# SAM9X60_Core.net
KiCad netlist of a schematic drawn in Altium Designer
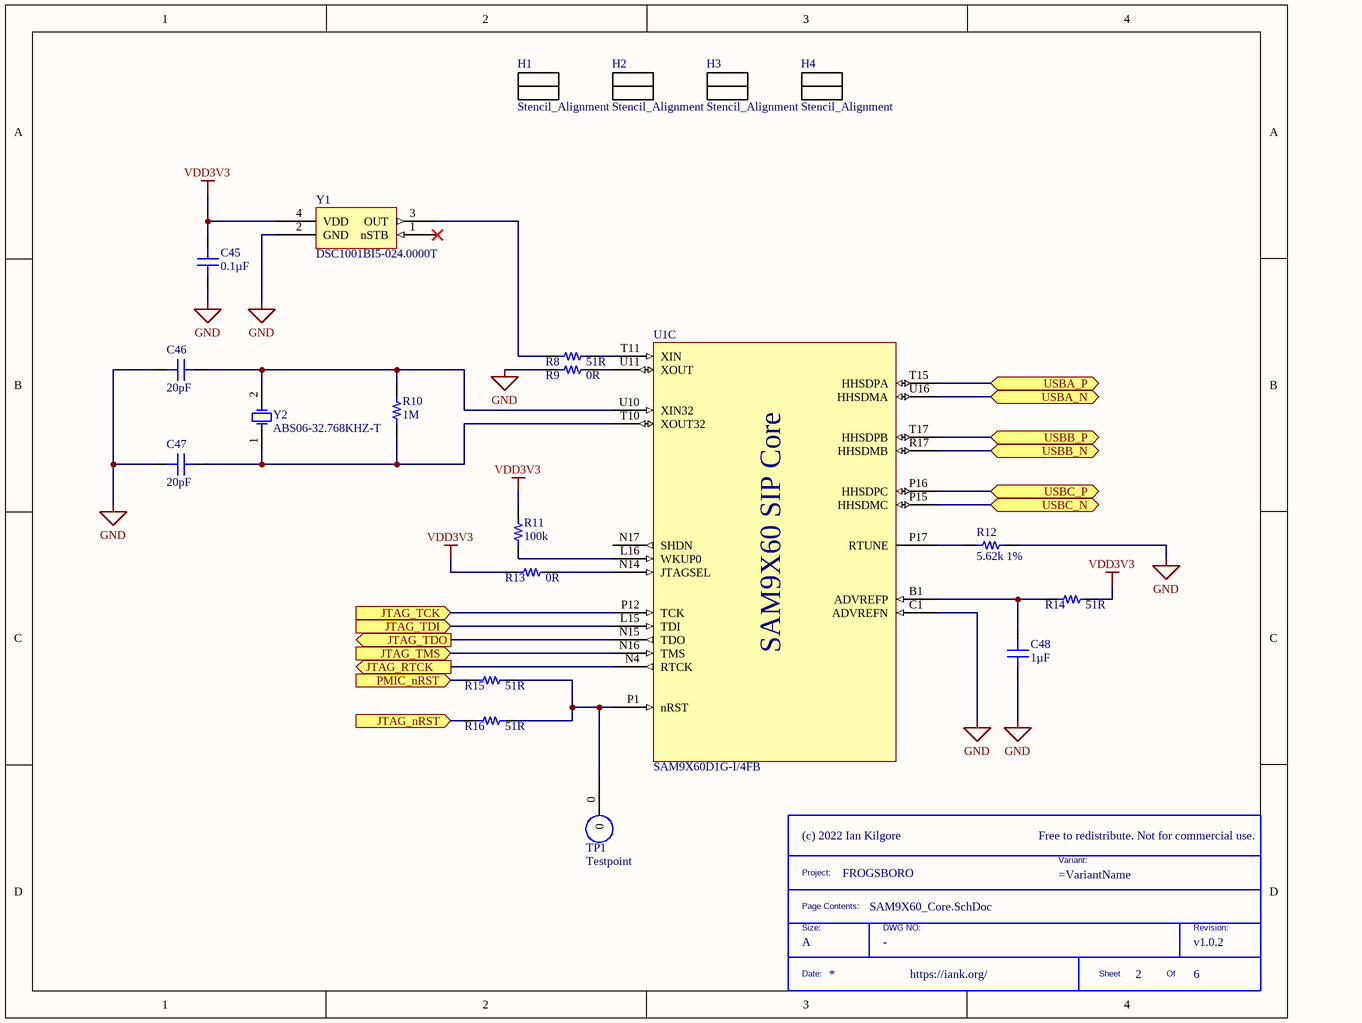
[diagram p0: SAM9X60_Core.SchDoc]

(export (version "E")
  (design (tool "Eeschema 10.0.6"))
  (components
    (comp (ref "C45")
      (value "0.1µF")
      (footprint "CAP 0402_1005")
      (description "CAP CER 0.1UF 16V X5R 0402")
      (fields (field (name "PART NUMBER") "C0402C104K4PACTU") (field (name "MANUFACTURER") "KEMET"))
      (libsource (lib "Celestial Altium Library - altium_library") (part "Capacitor"))
    )
    (comp (ref "C46")
      (value "20pF")
      (footprint "CAP 0402_1005")
      (description "CAP CER 20PF 50V C0G/NP0 0402")
      (fields
        (field (name "PART NUMBER") "GJM1555C1H200FB01D")
        (field (name "MANUFACTURER") "Murata Electronics")
      )
      (libsource (lib "Celestial Altium Library - altium_library") (part "Capacitor"))
    )
    (comp (ref "C47")
      (value "20pF")
      (footprint "CAP 0402_1005")
      (description "CAP CER 20PF 50V C0G/NP0 0402")
      (fields
        (field (name "PART NUMBER") "GJM1555C1H200FB01D")
        (field (name "MANUFACTURER") "Murata Electronics")
      )
      (libsource (lib "Celestial Altium Library - altium_library") (part "Capacitor"))
    )
    (comp (ref "C48")
      (value "1µF")
      (footprint "CAP 0402_1005")
      (description "CAP CER 1UF 10V X5R 0402")
      (fields (field (name "PART NUMBER") "0402ZD105KAT2A") (field (name "MANUFACTURER") "AVX Corporation"))
      (libsource (lib "Celestial Altium Library - altium_library") (part "Capacitor"))
    )
    (comp (ref "H1")
      (value "Stencil_Alignment")
      (footprint "Stencil_Alignment")
      (libsource (lib "FROGSBORO") (part "Stencil_Alignment"))
    )
    (comp (ref "H2")
      (value "Stencil_Alignment")
      (footprint "Stencil_Alignment")
      (libsource (lib "FROGSBORO") (part "Stencil_Alignment"))
    )
    (comp (ref "H3")
      (value "Stencil_Alignment")
      (footprint "Stencil_Alignment")
      (libsource (lib "FROGSBORO") (part "Stencil_Alignment"))
    )
    (comp (ref "H4")
      (value "Stencil_Alignment")
      (footprint "Stencil_Alignment")
      (libsource (lib "FROGSBORO") (part "Stencil_Alignment"))
    )
    (comp (ref "R8")
      (value "51R")
      (footprint "RES 0402_1005")
      (description "RES SMD 51 OHM 1% 1/16W 0402")
      (fields (field (name "PART NUMBER") "AC0402FR-0751RL") (field (name "MANUFACTURER") "Yageo"))
      (libsource (lib "Celestial Altium Library - altium_library") (part "Resistor"))
    )
    (comp (ref "R9")
      (value "0R")
      (footprint "RES 0402_1005")
      (description "RES SMD 0 OHM JUMPER 1/16W 0402")
      (fields
        (field (name "PART NUMBER") "CRG0402ZR")
        (field (name "MANUFACTURER") "TE Connectivity Passive Product")
      )
      (libsource (lib "Celestial Altium Library - altium_library") (part "Resistor"))
    )
    (comp (ref "R10")
      (value "1M")
      (footprint "RES 0402_1005")
      (description "RES SMD 1M OHM 5% 1/5W 0402")
      (fields (field (name "PART NUMBER") "RCS04021M00JNED") (field (name "MANUFACTURER") "Vishay Dale"))
      (libsource (lib "Celestial Altium Library - altium_library") (part "Resistor"))
    )
    (comp (ref "R11")
      (value "100k")
      (footprint "RES 0402_1005")
      (description "RES SMD 100K OHM 1% 1/16W 0402")
      (fields (field (name "PART NUMBER") "CRCW0402100KFKEDC") (field (name "MANUFACTURER") "Vishay Dale"))
      (libsource (lib "Celestial Altium Library - altium_library") (part "Resistor"))
    )
    (comp (ref "R12")
      (value "5.62k 1%")
      (footprint "RES 0402_1005")
      (description "RES SMD 5.62K OHM 1% 1/16W 0402")
      (fields (field (name "PART NUMBER") "AC0402FR-075K62L") (field (name "MANUFACTURER") "Yageo"))
      (libsource (lib "Celestial Altium Library - altium_library") (part "Resistor"))
    )
    (comp (ref "R13")
      (value "0R")
      (footprint "RES 0402_1005")
      (description "RES SMD 0 OHM JUMPER 1/16W 0402")
      (fields
        (field (name "PART NUMBER") "CRG0402ZR")
        (field (name "MANUFACTURER") "TE Connectivity Passive Product")
      )
      (libsource (lib "Celestial Altium Library - altium_library") (part "Resistor"))
    )
    (comp (ref "R14")
      (value "51R")
      (footprint "RES 0402_1005")
      (description "RES SMD 51 OHM 1% 1/16W 0402")
      (fields (field (name "PART NUMBER") "AC0402FR-0751RL") (field (name "MANUFACTURER") "Yageo"))
      (libsource (lib "Celestial Altium Library - altium_library") (part "Resistor"))
    )
    (comp (ref "R15")
      (value "51R")
      (footprint "RES 0402_1005")
      (description "RES SMD 51 OHM 1% 1/16W 0402")
      (fields (field (name "PART NUMBER") "AC0402FR-0751RL") (field (name "MANUFACTURER") "Yageo"))
      (libsource (lib "Celestial Altium Library - altium_library") (part "Resistor"))
    )
    (comp (ref "R16")
      (value "51R")
      (footprint "RES 0402_1005")
      (description "RES SMD 51 OHM 1% 1/16W 0402")
      (fields (field (name "PART NUMBER") "AC0402FR-0751RL") (field (name "MANUFACTURER") "Yageo"))
      (libsource (lib "Celestial Altium Library - altium_library") (part "Resistor"))
    )
    (comp (ref "TP1")
      (value "Testpoint")
      (footprint "FROGSBORO:Testpoint")
      (libsource (lib "FROGSBORO") (part "Testpoint"))
    )
    (comp (ref "U1")
      (value "SAM9X60D1G-I/4FB")
      (footprint "FROGSBORO:BGA233C80P17X17_1400X1400X120")
      (description "ARM926 MPU, 1GBIT DDR2, BGA, IND TEMP")
      (fields
        (field (name "MANUFACTURER") "Microchip")
        (field (name "MANUFACTURER PART NUMBER") "SAM9X60D6K-I/4GB")
      )
      (libsource (lib "FROGSBORO") (part "SAM9X60D1G-I/4FB"))
    )
    (comp (ref "Y1")
      (value "DSC1001BI5-024.0000T")
      (footprint "FROGSBORO:DSC1001BI5")
      (description "Low-Power Precision CMOS Oscillator 24MHz 1.7V to 3.6V 10ppm 4-Pin Surface Mount T/R")
      (fields (field (name "MANUFACTURER") "Microchip"))
      (libsource (lib "FROGSBORO") (part "DSC1001BI5-024.0000T"))
    )
    (comp (ref "Y2")
      (value "ABS06-32.768KHZ-T")
      (footprint "ABRA-ABS06-2_V")
      (description "Low Profile Crystal, 32.768 KHz, -40 to 85 degC, 2-Pin SMD, RoHS, Tape and Reel")
      (fields (field (name "TOLERANCE") "20PPM") (field (name "MANUFACTURER") "ABRACON"))
      (libsource (lib "Altium Content Vault") (part "XTAL_1-2-2"))
    )
  )
  (nets
    (net (code "1") (name "/JTAG_RTCK") (class "Default")
      (node (ref "U1") (pin "N4") (pinfunction "RTCK_N4") (pintype "output"))
    )
    (net (code "2") (name "/JTAG_TCK") (class "Default")
      (node (ref "U1") (pin "P12") (pinfunction "TCK_P12") (pintype "input"))
    )
    (net (code "3") (name "/JTAG_TDI") (class "Default")
      (node (ref "U1") (pin "L15") (pinfunction "TDI_L15") (pintype "input"))
    )
    (net (code "4") (name "/JTAG_TDO") (class "Default")
      (node (ref "U1") (pin "N15") (pinfunction "TDO_N15") (pintype "output"))
    )
    (net (code "5") (name "/JTAG_TMS") (class "Default")
      (node (ref "U1") (pin "N16") (pinfunction "TMS_N16") (pintype "input"))
    )
    (net (code "6") (name "/JTAG_nRST") (class "Default")
      (node (ref "R16") (pin "1") (pinfunction "1_1") (pintype "passive"))
    )
    (net (code "7") (name "/PMIC_nRST") (class "Default")
      (node (ref "R15") (pin "1") (pinfunction "1_1") (pintype "passive"))
    )
    (net (code "8") (name "/USBA_N") (class "Default")
      (node (ref "U1") (pin "U16") (pinfunction "HHSDMA_U16") (pintype "bidirectional"))
    )
    (net (code "9") (name "/USBA_P") (class "Default")
      (node (ref "U1") (pin "T15") (pinfunction "HHSDPA_T15") (pintype "bidirectional"))
    )
    (net (code "10") (name "/USBB_N") (class "Default")
      (node (ref "U1") (pin "R17") (pinfunction "HHSDMB_R17") (pintype "bidirectional"))
    )
    (net (code "11") (name "/USBB_P") (class "Default")
      (node (ref "U1") (pin "T17") (pinfunction "HHSDPB_T17") (pintype "bidirectional"))
    )
    (net (code "12") (name "/USBC_N") (class "Default")
      (node (ref "U1") (pin "P15") (pinfunction "HHSDMC_P15") (pintype "bidirectional"))
    )
    (net (code "13") (name "/USBC_P") (class "Default")
      (node (ref "U1") (pin "P16") (pinfunction "HHSDPC_P16") (pintype "bidirectional"))
    )
    (net (code "14") (name "GND") (class "Default")
      (node (ref "C45") (pin "2") (pinfunction "2_2") (pintype "passive"))
      (node (ref "C46") (pin "1") (pinfunction "1_1") (pintype "passive"))
      (node (ref "C47") (pin "1") (pinfunction "1_1") (pintype "passive"))
      (node (ref "C48") (pin "1") (pinfunction "1_1") (pintype "passive"))
      (node (ref "R12") (pin "2") (pinfunction "2_2") (pintype "passive"))
      (node (ref "R9") (pin "1") (pinfunction "1_1") (pintype "passive"))
      (node (ref "U1") (pin "C1") (pinfunction "ADVREFN_C1") (pintype "input"))
      (node (ref "Y1") (pin "2") (pinfunction "GND_2") (pintype "power_in"))
    )
    (net (code "15") (name "Net-(U1C-ADVREFP)") (class "Default")
      (node (ref "C48") (pin "2") (pinfunction "2_2") (pintype "passive"))
      (node (ref "R14") (pin "1") (pinfunction "1_1") (pintype "passive"))
      (node (ref "U1") (pin "B1") (pinfunction "ADVREFP_B1") (pintype "input"))
    )
    (net (code "16") (name "Net-(U1C-JTAGSEL)") (class "Default")
      (node (ref "R13") (pin "2") (pinfunction "2_2") (pintype "passive"))
      (node (ref "U1") (pin "N14") (pinfunction "JTAGSEL_N14") (pintype "input"))
    )
    (net (code "17") (name "Net-(U1C-RTUNE)") (class "Default")
      (node (ref "R12") (pin "1") (pinfunction "1_1") (pintype "passive"))
      (node (ref "U1") (pin "P17") (pinfunction "RTUNE_P17") (pintype "passive"))
    )
    (net (code "18") (name "Net-(U1C-WKUP0)") (class "Default")
      (node (ref "R11") (pin "1") (pinfunction "1_1") (pintype "passive"))
      (node (ref "U1") (pin "L16") (pinfunction "WKUP0_L16") (pintype "input"))
    )
    (net (code "19") (name "Net-(U1C-XIN)") (class "Default")
      (node (ref "R8") (pin "2") (pinfunction "2_2") (pintype "passive"))
      (node (ref "U1") (pin "T11") (pinfunction "XIN_T11") (pintype "input"))
    )
    (net (code "20") (name "Net-(U1C-XIN32)") (class "Default")
      (node (ref "C46") (pin "2") (pinfunction "2_2") (pintype "passive"))
      (node (ref "R10") (pin "2") (pinfunction "2_2") (pintype "passive"))
      (node (ref "U1") (pin "U10") (pinfunction "XIN32_U10") (pintype "input"))
      (node (ref "Y2") (pin "2") (pinfunction "X2_2") (pintype "passive"))
    )
    (net (code "21") (name "Net-(U1C-XOUT)") (class "Default")
      (node (ref "R9") (pin "2") (pinfunction "2_2") (pintype "passive"))
      (node (ref "U1") (pin "U11") (pinfunction "XOUT_U11") (pintype "bidirectional"))
    )
    (net (code "22") (name "Net-(U1C-XOUT32)") (class "Default")
      (node (ref "C47") (pin "2") (pinfunction "2_2") (pintype "passive"))
      (node (ref "R10") (pin "1") (pinfunction "1_1") (pintype "passive"))
      (node (ref "U1") (pin "T10") (pinfunction "XOUT32_T10") (pintype "bidirectional"))
      (node (ref "Y2") (pin "1") (pinfunction "X1_1") (pintype "passive"))
    )
    (net (code "23") (name "Net-(U1C-nRST)") (class "Default")
      (node (ref "R15") (pin "2") (pinfunction "2_2") (pintype "passive"))
      (node (ref "R16") (pin "2") (pinfunction "2_2") (pintype "passive"))
      (node (ref "TP1") (pin "0") (pinfunction "0_0") (pintype "passive"))
      (node (ref "U1") (pin "P1") (pinfunction "nRST_P1") (pintype "input"))
    )
    (net (code "24") (name "Net-(Y1-OUT)") (class "Default")
      (node (ref "R8") (pin "1") (pinfunction "1_1") (pintype "passive"))
      (node (ref "Y1") (pin "3") (pinfunction "OUT_3") (pintype "output"))
    )
    (net (code "25") (name "VDD3V3") (class "Default")
      (node (ref "C45") (pin "1") (pinfunction "1_1") (pintype "passive"))
      (node (ref "R11") (pin "2") (pinfunction "2_2") (pintype "passive"))
      (node (ref "R13") (pin "1") (pinfunction "1_1") (pintype "passive"))
      (node (ref "R14") (pin "2") (pinfunction "2_2") (pintype "passive"))
      (node (ref "Y1") (pin "4") (pinfunction "VDD_4") (pintype "power_in"))
    )
    (net (code "26") (name "unconnected-(H1-Pad0)") (class "Default")
      (node (ref "H1") (pin "0") (pinfunction "0_0") (pintype "passive"))
    )
    (net (code "27") (name "unconnected-(H2-Pad0)") (class "Default")
      (node (ref "H2") (pin "0") (pinfunction "0_0") (pintype "passive"))
    )
    (net (code "28") (name "unconnected-(H3-Pad0)") (class "Default")
      (node (ref "H3") (pin "0") (pinfunction "0_0") (pintype "passive"))
    )
    (net (code "29") (name "unconnected-(H4-Pad0)") (class "Default")
      (node (ref "H4") (pin "0") (pinfunction "0_0") (pintype "passive"))
    )
    (net (code "30") (name "unconnected-(U1C-SHDN-PadN17)") (class "Default")
      (node (ref "U1") (pin "N17") (pinfunction "SHDN_N17") (pintype "output"))
    )
    (net (code "31") (name "unconnected-(Y1-nSTB-Pad1)") (class "Default")
      (node (ref "Y1") (pin "1") (pinfunction "nSTB_1") (pintype "input+no_connect"))
    )
  )
)
